# sensors_r.net
KiCad netlist of a schematic drawn in EAGLE
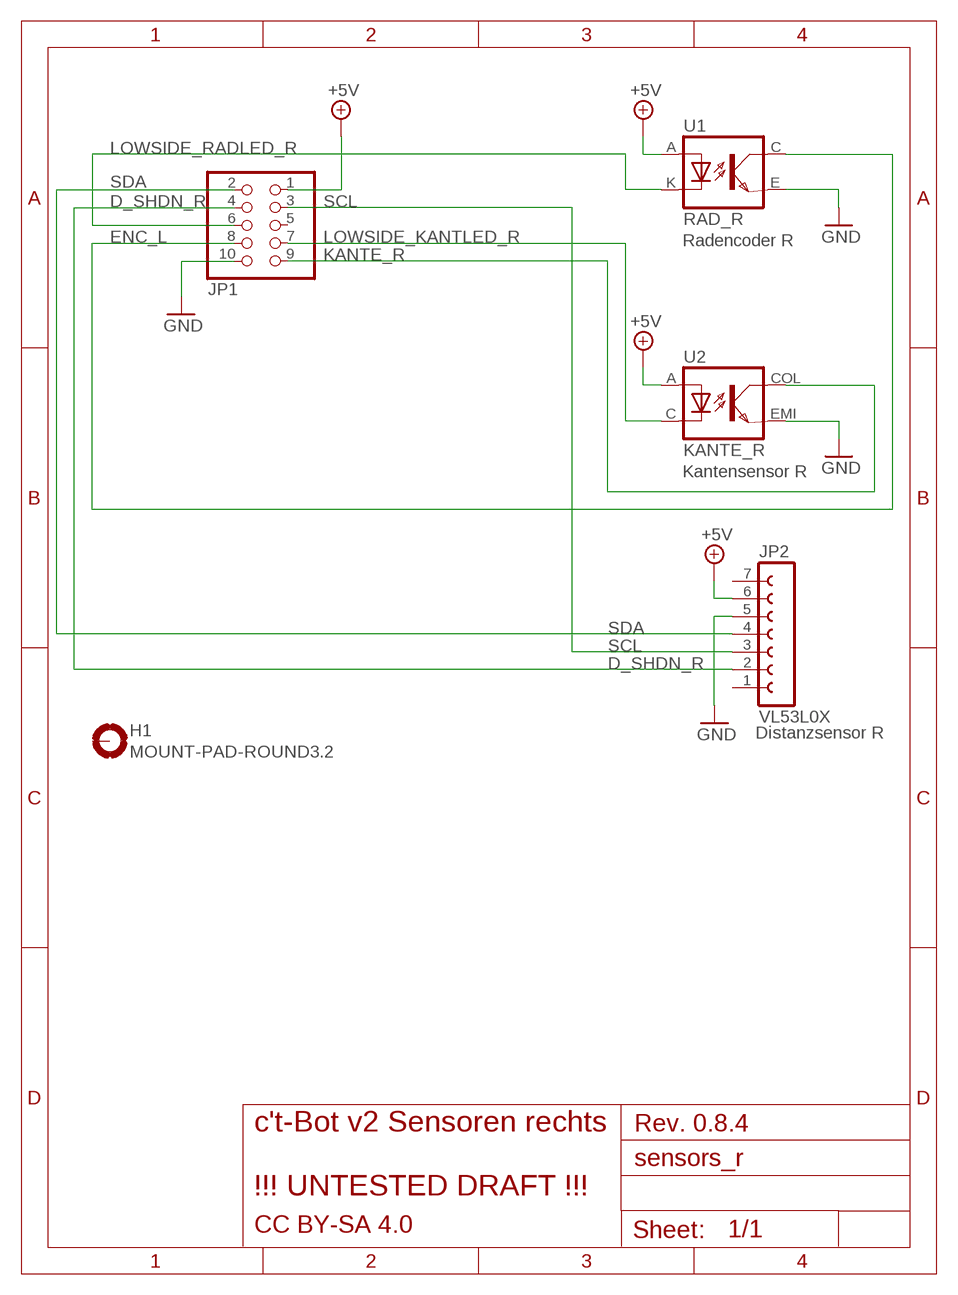
[diagram p0: schematic, sheet 1]

(export (version "E")
  (design (tool "Eeschema 10.0.6"))
  (components
    (comp (ref "H1")
      (value "MOUNT-PAD-ROUND3.2")
      (footprint "eagle-import:3,2-PAD")
      (libsource (lib "eagle-import") (part "MOUNT-PAD-ROUND3.2"))
    )
    (comp (ref "JP1")
      (value "PINHD-2X5")
      (footprint "eagle-import:2X05")
      (libsource (lib "eagle-import") (part "PINHD-2X5"))
    )
    (comp (ref "JP2")
      (value "VL53L0X")
      (footprint "eagle-import:FE07W")
      (libsource (lib "eagle-import") (part "FE07W"))
    )
    (comp (ref "U1")
      (value "RAD_R")
      (footprint "eagle-import:4")
      (libsource (lib "eagle-import") (part "CNY70DEF"))
    )
    (comp (ref "U2")
      (value "KANTE_R")
      (footprint "eagle-import:EDGE")
      (libsource (lib "eagle-import") (part "CNY70"))
    )
  )
  (nets
    (net (code "1") (name "+5V") (class "Default")
      (node (ref "JP1") (pin "1") (pinfunction "1_1") (pintype "passive"))
      (node (ref "JP2") (pin "6") (pinfunction "6_6") (pintype "passive"))
      (node (ref "U1") (pin "A") (pinfunction "A_A") (pintype "passive"))
      (node (ref "U2") (pin "A") (pinfunction "A_A") (pintype "passive"))
    )
    (net (code "2") (name "/D_SHDN_R") (class "Default")
      (node (ref "JP1") (pin "4") (pinfunction "4_4") (pintype "passive"))
      (node (ref "JP2") (pin "2") (pinfunction "2_2") (pintype "passive"))
    )
    (net (code "3") (name "/ENC_L") (class "Default")
      (node (ref "JP1") (pin "8") (pinfunction "8_8") (pintype "passive"))
      (node (ref "U1") (pin "C") (pinfunction "COL_C") (pintype "passive"))
    )
    (net (code "4") (name "/KANTE_R") (class "Default")
      (node (ref "JP1") (pin "9") (pinfunction "9_9") (pintype "passive"))
      (node (ref "U2") (pin "COL") (pinfunction "COL_COL") (pintype "passive"))
    )
    (net (code "5") (name "/LOWSIDE_KANTLED_R") (class "Default")
      (node (ref "JP1") (pin "7") (pinfunction "7_7") (pintype "passive"))
      (node (ref "U2") (pin "C") (pinfunction "C_C") (pintype "passive"))
    )
    (net (code "6") (name "/LOWSIDE_RADLED_R") (class "Default")
      (node (ref "JP1") (pin "6") (pinfunction "6_6") (pintype "passive"))
      (node (ref "U1") (pin "K") (pinfunction "C_K") (pintype "passive"))
    )
    (net (code "7") (name "/SCL") (class "Default")
      (node (ref "JP1") (pin "3") (pinfunction "3_3") (pintype "passive"))
      (node (ref "JP2") (pin "3") (pinfunction "3_3") (pintype "passive"))
    )
    (net (code "8") (name "/SDA") (class "Default")
      (node (ref "JP1") (pin "2") (pinfunction "2_2") (pintype "passive"))
      (node (ref "JP2") (pin "4") (pinfunction "4_4") (pintype "passive"))
    )
    (net (code "9") (name "GND") (class "Default")
      (node (ref "JP1") (pin "10") (pinfunction "10_10") (pintype "passive"))
      (node (ref "JP2") (pin "5") (pinfunction "5_5") (pintype "passive"))
      (node (ref "U1") (pin "E") (pinfunction "EMI_E") (pintype "passive"))
      (node (ref "U2") (pin "EMI") (pinfunction "EMI_EMI") (pintype "passive"))
    )
    (net (code "10") (name "unconnected-(H1-MOUNT-PadB3,2)") (class "Default")
      (node (ref "H1") (pin "B3,2") (pinfunction "MOUNT_B3,2") (pintype "passive"))
    )
    (net (code "11") (name "unconnected-(JP1-Pad5)") (class "Default")
      (node (ref "JP1") (pin "5") (pinfunction "5_5") (pintype "passive"))
    )
    (net (code "12") (name "unconnected-(JP2-Pad1)") (class "Default")
      (node (ref "JP2") (pin "1") (pinfunction "1_1") (pintype "passive"))
    )
    (net (code "13") (name "unconnected-(JP2-Pad7)") (class "Default")
      (node (ref "JP2") (pin "7") (pinfunction "7_7") (pintype "passive"))
    )
  )
)
